# RadioMusic_B_Rev2.net
KiCad netlist of a schematic drawn in EAGLE
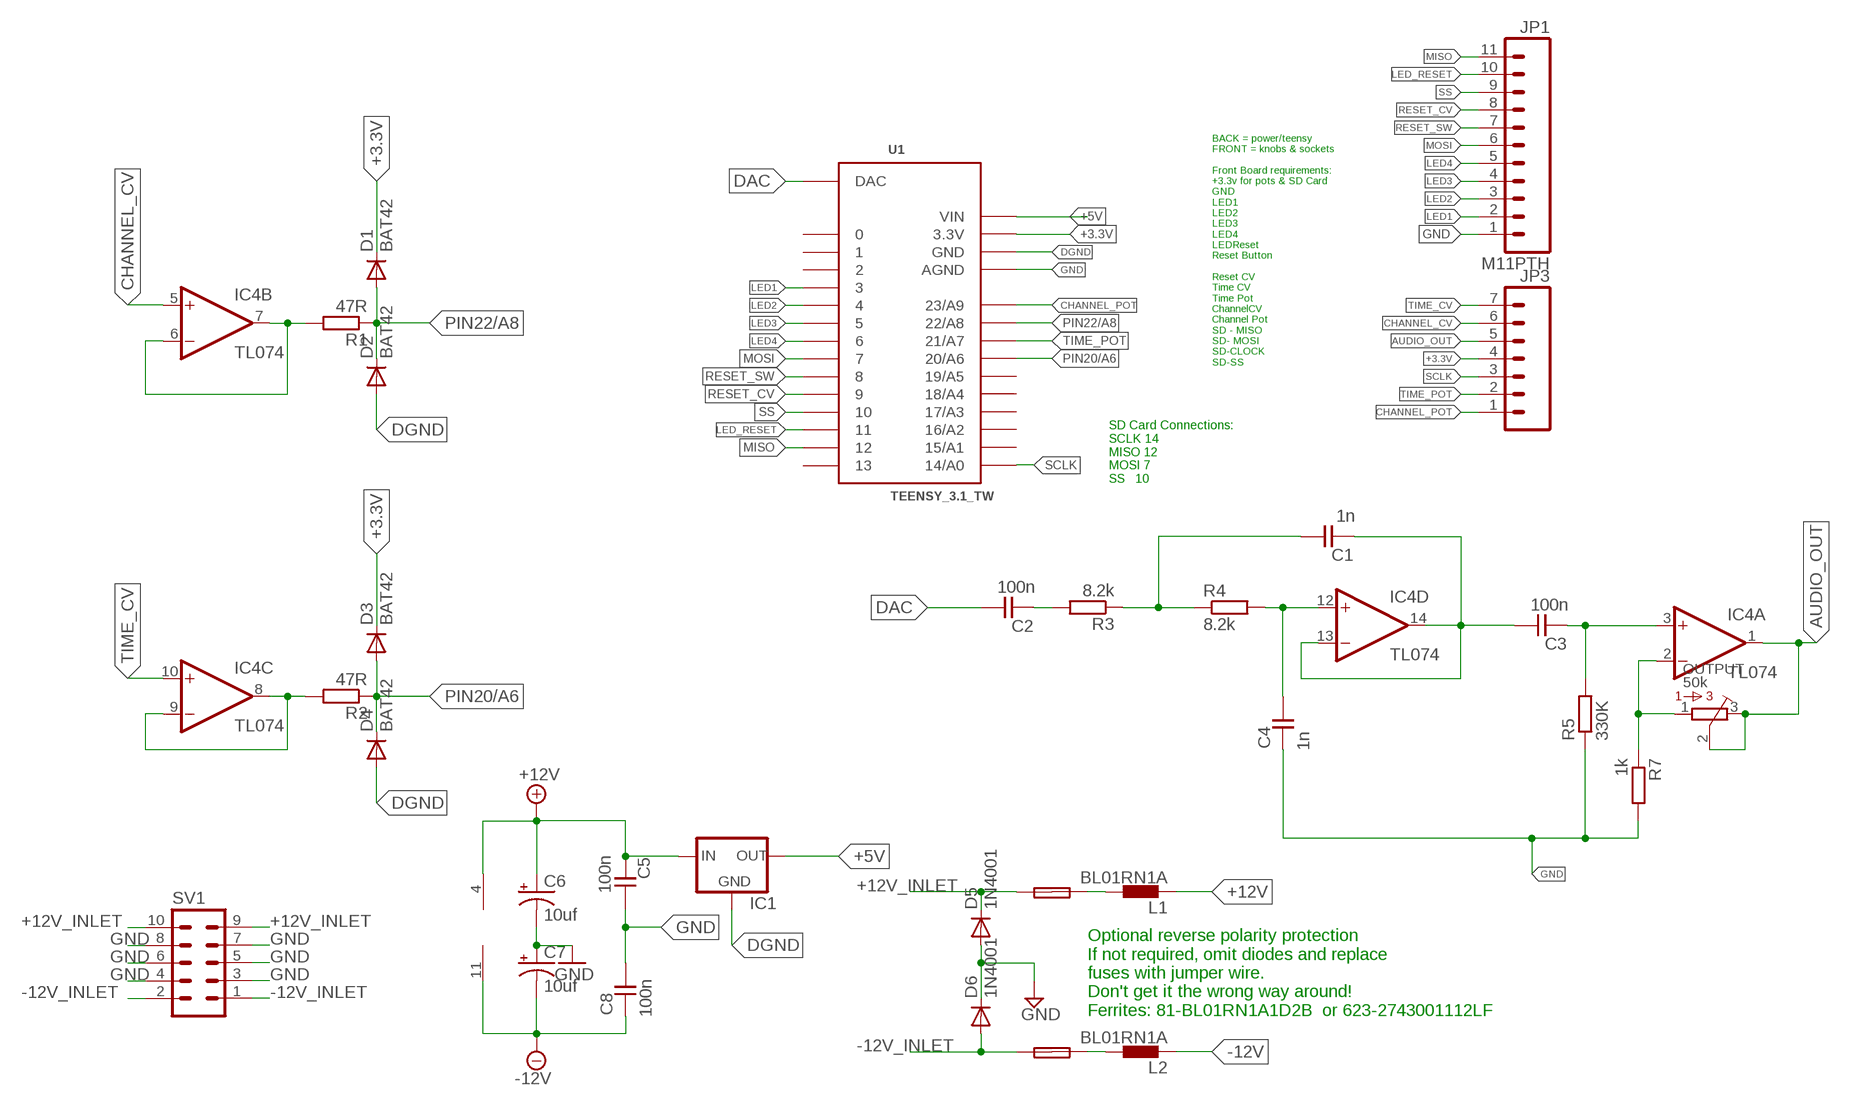
[diagram p0: schematic, sheet 1]

(export (version "E")
  (design (tool "Eeschema 10.0.6"))
  (components
    (comp (ref "C1")
      (value "1n")
      (footprint "eagle-import:C050-024X044")
      (libsource (lib "eagle-import") (part "C-EU050-024X044"))
    )
    (comp (ref "C2")
      (value "100n")
      (footprint "eagle-import:C050-025X075")
      (libsource (lib "eagle-import") (part "C-EU050-025X075"))
    )
    (comp (ref "C3")
      (value "100n")
      (footprint "eagle-import:C050-025X075")
      (libsource (lib "eagle-import") (part "C-EU050-025X075"))
    )
    (comp (ref "C4")
      (value "1n")
      (footprint "eagle-import:C050-024X044")
      (libsource (lib "eagle-import") (part "C-EU050-024X044"))
    )
    (comp (ref "C5")
      (value "100n")
      (footprint "eagle-import:C050-024X044")
      (libsource (lib "eagle-import") (part "C-EU050-024X044"))
    )
    (comp (ref "C6")
      (value "10uf")
      (footprint "eagle-import:CPOL-RADIAL-10UF-25V")
      (libsource (lib "eagle-import") (part "CAP_POLPTH2"))
    )
    (comp (ref "C7")
      (value "10uf")
      (footprint "eagle-import:CPOL-RADIAL-10UF-25V")
      (libsource (lib "eagle-import") (part "CAP_POLPTH2"))
    )
    (comp (ref "C8")
      (value "100n")
      (footprint "eagle-import:C050-024X044")
      (libsource (lib "eagle-import") (part "C-EU050-024X044"))
    )
    (comp (ref "D1")
      (value "BAT42")
      (footprint "eagle-import:DO34-7")
      (libsource (lib "eagle-import") (part "BAT81"))
    )
    (comp (ref "D2")
      (value "BAT42")
      (footprint "eagle-import:DO34-7")
      (libsource (lib "eagle-import") (part "BAT81"))
    )
    (comp (ref "D3")
      (value "BAT42")
      (footprint "eagle-import:DO34-7")
      (libsource (lib "eagle-import") (part "BAT81"))
    )
    (comp (ref "D4")
      (value "BAT42")
      (footprint "eagle-import:DO34-7")
      (libsource (lib "eagle-import") (part "BAT81"))
    )
    (comp (ref "D5")
      (value "1N4001")
      (footprint "eagle-import:DO41-10")
      (libsource (lib "eagle-import") (part "1N4004"))
    )
    (comp (ref "D6")
      (value "1N4001")
      (footprint "eagle-import:DO41-10")
      (libsource (lib "eagle-import") (part "1N4004"))
    )
    (comp (ref "F1")
      (value "FUSE")
      (footprint "eagle-import:C050H075X075")
      (libsource (lib "eagle-import") (part "PTC_FUSEPOLY_FUSE"))
    )
    (comp (ref "F2")
      (value "FUSE")
      (footprint "eagle-import:C050H075X075")
      (libsource (lib "eagle-import") (part "PTC_FUSEPOLY_FUSE"))
    )
    (comp (ref "IC1")
      (value "78LXX")
      (footprint "eagle-import:78LXX")
      (libsource (lib "eagle-import") (part "78LXX"))
    )
    (comp (ref "IC4")
      (value "TL074")
      (footprint "eagle-import:DIL14")
      (libsource (lib "eagle-import") (part "TL074P"))
    )
    (comp (ref "JP1")
      (value "M11PTH")
      (footprint "eagle-import:1X11")
      (libsource (lib "eagle-import") (part "M11PTH"))
    )
    (comp (ref "JP3")
      (value "M07")
      (footprint "eagle-import:1X07")
      (libsource (lib "eagle-import") (part "M07"))
    )
    (comp (ref "L1")
      (value "BL01RN1A")
      (footprint "eagle-import:BL01RN1A")
      (libsource (lib "eagle-import") (part "BL01RN1A"))
    )
    (comp (ref "L2")
      (value "BL01RN1A")
      (footprint "eagle-import:BL01RN1A")
      (libsource (lib "eagle-import") (part "BL01RN1A"))
    )
    (comp (ref "OUTPUT")
      (value "50k")
      (footprint "eagle-import:3362P")
      (libsource (lib "eagle-import") (part "3362P"))
    )
    (comp (ref "R1")
      (value "47R")
      (footprint "eagle-import:0207_10")
      (libsource (lib "eagle-import") (part "R-EU_STANDARD_RESISTOR"))
    )
    (comp (ref "R2")
      (value "47R")
      (footprint "eagle-import:0207_10")
      (libsource (lib "eagle-import") (part "R-EU_STANDARD_RESISTOR"))
    )
    (comp (ref "R3")
      (value "8.2k")
      (footprint "eagle-import:0207_10")
      (libsource (lib "eagle-import") (part "R-EU_STANDARD_RESISTOR"))
    )
    (comp (ref "R4")
      (value "8.2k")
      (footprint "eagle-import:0207_10")
      (libsource (lib "eagle-import") (part "R-EU_STANDARD_RESISTOR"))
    )
    (comp (ref "R5")
      (value "330K")
      (footprint "eagle-import:0207_10")
      (libsource (lib "eagle-import") (part "R-EU_STANDARD_RESISTOR"))
    )
    (comp (ref "R7")
      (value "1k")
      (footprint "eagle-import:0207_10")
      (libsource (lib "eagle-import") (part "R-EU_STANDARD_RESISTOR"))
    )
    (comp (ref "SV1")
      (value "10_PIN_HEADER")
      (footprint "eagle-import:MA05-2")
      (libsource (lib "eagle-import") (part "10_PIN_HEADER"))
    )
    (comp (ref "U1")
      (value "TEENSY_3.1_TW")
      (footprint "eagle-import:TEENSY_3.1_TW")
      (libsource (lib "eagle-import") (part "TEENSY_3.1_TW"))
    )
  )
  (nets
    (net (code "1") (name "+3.3V") (class "Default")
      (node (ref "D1") (pin "C") (pinfunction "C_C") (pintype "passive"))
      (node (ref "D3") (pin "C") (pinfunction "C_C") (pintype "passive"))
      (node (ref "JP3") (pin "4") (pinfunction "4_4") (pintype "passive"))
      (node (ref "U1") (pin "3.3V") (pinfunction "3.3V_3.3V") (pintype "power_in"))
    )
    (net (code "2") (name "+5V") (class "Default")
      (node (ref "IC1") (pin "OUT") (pinfunction "OUT_OUT") (pintype "passive"))
      (node (ref "U1") (pin "VIN") (pinfunction "VIN_VIN") (pintype "power_in"))
    )
    (net (code "3") (name "+12V") (class "Default")
      (node (ref "C5") (pin "2") (pinfunction "2_2") (pintype "passive"))
      (node (ref "C6") (pin "1") (pinfunction "+_1") (pintype "passive"))
      (node (ref "IC1") (pin "IN") (pinfunction "IN_IN") (pintype "input"))
      (node (ref "IC4") (pin "4") (pinfunction "V+_4") (pintype "power_in"))
      (node (ref "L1") (pin "1") (pinfunction "1_1") (pintype "passive"))
    )
    (net (code "4") (name "-12V") (class "Default")
      (node (ref "C7") (pin "2") (pinfunction "-_2") (pintype "passive"))
      (node (ref "C8") (pin "2") (pinfunction "2_2") (pintype "passive"))
      (node (ref "IC4") (pin "11") (pinfunction "V-_11") (pintype "power_in"))
      (node (ref "L2") (pin "1") (pinfunction "1_1") (pintype "passive"))
    )
    (net (code "5") (name "/+12V_INLET") (class "Default")
      (node (ref "D5") (pin "C") (pinfunction "C_C") (pintype "passive"))
      (node (ref "F1") (pin "1") (pinfunction "P$1_1") (pintype "bidirectional"))
      (node (ref "SV1") (pin "10") (pinfunction "10_10") (pintype "passive"))
      (node (ref "SV1") (pin "9") (pinfunction "9_9") (pintype "passive"))
    )
    (net (code "6") (name "/-12V_INLET") (class "Default")
      (node (ref "D6") (pin "A") (pinfunction "A_A") (pintype "passive"))
      (node (ref "F2") (pin "1") (pinfunction "P$1_1") (pintype "bidirectional"))
      (node (ref "SV1") (pin "1") (pinfunction "1_1") (pintype "passive"))
      (node (ref "SV1") (pin "2") (pinfunction "2_2") (pintype "passive"))
    )
    (net (code "7") (name "AUDIO_OUT") (class "Default")
      (node (ref "IC4") (pin "1") (pinfunction "OUT_1") (pintype "output"))
      (node (ref "JP3") (pin "5") (pinfunction "5_5") (pintype "passive"))
      (node (ref "OUTPUT") (pin "2") (pinfunction "2_2") (pintype "passive"))
      (node (ref "OUTPUT") (pin "3") (pinfunction "3_3") (pintype "passive"))
    )
    (net (code "8") (name "CHANNEL_CV") (class "Default")
      (node (ref "IC4") (pin "5") (pinfunction "+IN_5") (pintype "input"))
      (node (ref "JP3") (pin "6") (pinfunction "6_6") (pintype "passive"))
    )
    (net (code "9") (name "CHANNEL_POT") (class "Default")
      (node (ref "JP3") (pin "1") (pinfunction "1_1") (pintype "passive"))
      (node (ref "U1") (pin "23/A9") (pinfunction "23/A9_23/A9") (pintype "bidirectional"))
    )
    (net (code "10") (name "DAC") (class "Default")
      (node (ref "C2") (pin "1") (pinfunction "1_1") (pintype "passive"))
      (node (ref "U1") (pin "DAC") (pinfunction "DAC_DAC") (pintype "bidirectional"))
    )
    (net (code "11") (name "DGND") (class "Default")
      (node (ref "D2") (pin "A") (pinfunction "A_A") (pintype "passive"))
      (node (ref "D4") (pin "A") (pinfunction "A_A") (pintype "passive"))
      (node (ref "IC1") (pin "GND") (pinfunction "GND_GND") (pintype "input"))
      (node (ref "U1") (pin "GND") (pinfunction "GND_GND") (pintype "power_in"))
    )
    (net (code "12") (name "GND") (class "Default")
      (node (ref "C4") (pin "2") (pinfunction "2_2") (pintype "passive"))
      (node (ref "C5") (pin "1") (pinfunction "1_1") (pintype "passive"))
      (node (ref "C6") (pin "2") (pinfunction "-_2") (pintype "passive"))
      (node (ref "C7") (pin "1") (pinfunction "+_1") (pintype "passive"))
      (node (ref "C8") (pin "1") (pinfunction "1_1") (pintype "passive"))
      (node (ref "D5") (pin "A") (pinfunction "A_A") (pintype "passive"))
      (node (ref "D6") (pin "C") (pinfunction "C_C") (pintype "passive"))
      (node (ref "JP1") (pin "1") (pinfunction "1_1") (pintype "passive"))
      (node (ref "R5") (pin "1") (pinfunction "1_1") (pintype "passive"))
      (node (ref "R7") (pin "2") (pinfunction "2_2") (pintype "passive"))
      (node (ref "SV1") (pin "3") (pinfunction "3_3") (pintype "passive"))
      (node (ref "SV1") (pin "4") (pinfunction "4_4") (pintype "passive"))
      (node (ref "SV1") (pin "5") (pinfunction "5_5") (pintype "passive"))
      (node (ref "SV1") (pin "6") (pinfunction "6_6") (pintype "passive"))
      (node (ref "SV1") (pin "7") (pinfunction "7_7") (pintype "passive"))
      (node (ref "SV1") (pin "8") (pinfunction "8_8") (pintype "passive"))
      (node (ref "U1") (pin "AGND") (pinfunction "AGND_AGND") (pintype "power_in"))
    )
    (net (code "13") (name "LED1") (class "Default")
      (node (ref "JP1") (pin "2") (pinfunction "2_2") (pintype "passive"))
      (node (ref "U1") (pin "3") (pinfunction "3_3") (pintype "bidirectional"))
    )
    (net (code "14") (name "LED2") (class "Default")
      (node (ref "JP1") (pin "3") (pinfunction "3_3") (pintype "passive"))
      (node (ref "U1") (pin "4") (pinfunction "4_4") (pintype "bidirectional"))
    )
    (net (code "15") (name "LED3") (class "Default")
      (node (ref "JP1") (pin "4") (pinfunction "4_4") (pintype "passive"))
      (node (ref "U1") (pin "5") (pinfunction "5_5") (pintype "bidirectional"))
    )
    (net (code "16") (name "LED4") (class "Default")
      (node (ref "JP1") (pin "5") (pinfunction "5_5") (pintype "passive"))
      (node (ref "U1") (pin "6") (pinfunction "6_6") (pintype "bidirectional"))
    )
    (net (code "17") (name "LED_RESET") (class "Default")
      (node (ref "JP1") (pin "10") (pinfunction "10_10") (pintype "passive"))
      (node (ref "U1") (pin "11") (pinfunction "11_11") (pintype "bidirectional"))
    )
    (net (code "18") (name "MISO") (class "Default")
      (node (ref "JP1") (pin "11") (pinfunction "11_11") (pintype "passive"))
      (node (ref "U1") (pin "12") (pinfunction "12_12") (pintype "bidirectional"))
    )
    (net (code "19") (name "MOSI") (class "Default")
      (node (ref "JP1") (pin "6") (pinfunction "6_6") (pintype "passive"))
      (node (ref "U1") (pin "7") (pinfunction "7_7") (pintype "bidirectional"))
    )
    (net (code "20") (name "Net-(C1-Pad1)") (class "Default")
      (node (ref "C1") (pin "1") (pinfunction "1_1") (pintype "passive"))
      (node (ref "R3") (pin "1") (pinfunction "1_1") (pintype "passive"))
      (node (ref "R4") (pin "1") (pinfunction "1_1") (pintype "passive"))
    )
    (net (code "21") (name "Net-(C2-Pad2)") (class "Default")
      (node (ref "C2") (pin "2") (pinfunction "2_2") (pintype "passive"))
      (node (ref "R3") (pin "2") (pinfunction "2_2") (pintype "passive"))
    )
    (net (code "22") (name "Net-(F1-P$2)") (class "Default")
      (node (ref "F1") (pin "2") (pinfunction "P$2_2") (pintype "bidirectional"))
      (node (ref "L1") (pin "2") (pinfunction "2_2") (pintype "passive"))
    )
    (net (code "23") (name "Net-(F2-P$2)") (class "Default")
      (node (ref "F2") (pin "2") (pinfunction "P$2_2") (pintype "bidirectional"))
      (node (ref "L2") (pin "2") (pinfunction "2_2") (pintype "passive"))
    )
    (net (code "24") (name "Net-(IC4A-+IN)") (class "Default")
      (node (ref "C3") (pin "2") (pinfunction "2_2") (pintype "passive"))
      (node (ref "IC4") (pin "3") (pinfunction "+IN_3") (pintype "input"))
      (node (ref "R5") (pin "2") (pinfunction "2_2") (pintype "passive"))
    )
    (net (code "25") (name "Net-(IC4A--IN)") (class "Default")
      (node (ref "IC4") (pin "2") (pinfunction "-IN_2") (pintype "input"))
      (node (ref "OUTPUT") (pin "1") (pinfunction "1_1") (pintype "passive"))
      (node (ref "R7") (pin "1") (pinfunction "1_1") (pintype "passive"))
    )
    (net (code "26") (name "Net-(IC4B--IN)") (class "Default")
      (node (ref "IC4") (pin "6") (pinfunction "-IN_6") (pintype "input"))
      (node (ref "IC4") (pin "7") (pinfunction "OUT_7") (pintype "output"))
      (node (ref "R1") (pin "2") (pinfunction "2_2") (pintype "passive"))
    )
    (net (code "27") (name "Net-(IC4C--IN)") (class "Default")
      (node (ref "IC4") (pin "8") (pinfunction "OUT_8") (pintype "output"))
      (node (ref "IC4") (pin "9") (pinfunction "-IN_9") (pintype "input"))
      (node (ref "R2") (pin "2") (pinfunction "2_2") (pintype "passive"))
    )
    (net (code "28") (name "Net-(IC4D-+IN)") (class "Default")
      (node (ref "C4") (pin "1") (pinfunction "1_1") (pintype "passive"))
      (node (ref "IC4") (pin "12") (pinfunction "+IN_12") (pintype "input"))
      (node (ref "R4") (pin "2") (pinfunction "2_2") (pintype "passive"))
    )
    (net (code "29") (name "Net-(IC4D--IN)") (class "Default")
      (node (ref "C1") (pin "2") (pinfunction "2_2") (pintype "passive"))
      (node (ref "C3") (pin "1") (pinfunction "1_1") (pintype "passive"))
      (node (ref "IC4") (pin "13") (pinfunction "-IN_13") (pintype "input"))
      (node (ref "IC4") (pin "14") (pinfunction "OUT_14") (pintype "output"))
    )
    (net (code "30") (name "PIN20{slash}A6") (class "Default")
      (node (ref "D3") (pin "A") (pinfunction "A_A") (pintype "passive"))
      (node (ref "D4") (pin "C") (pinfunction "C_C") (pintype "passive"))
      (node (ref "R2") (pin "1") (pinfunction "1_1") (pintype "passive"))
      (node (ref "U1") (pin "20/A6") (pinfunction "20/A6_20/A6") (pintype "bidirectional"))
    )
    (net (code "31") (name "PIN22{slash}A8") (class "Default")
      (node (ref "D1") (pin "A") (pinfunction "A_A") (pintype "passive"))
      (node (ref "D2") (pin "C") (pinfunction "C_C") (pintype "passive"))
      (node (ref "R1") (pin "1") (pinfunction "1_1") (pintype "passive"))
      (node (ref "U1") (pin "22/A8") (pinfunction "22/A8_22/A8") (pintype "bidirectional"))
    )
    (net (code "32") (name "RESET_CV") (class "Default")
      (node (ref "JP1") (pin "8") (pinfunction "8_8") (pintype "passive"))
      (node (ref "U1") (pin "9") (pinfunction "9_9") (pintype "bidirectional"))
    )
    (net (code "33") (name "RESET_SW") (class "Default")
      (node (ref "JP1") (pin "7") (pinfunction "7_7") (pintype "passive"))
      (node (ref "U1") (pin "8") (pinfunction "8_8") (pintype "bidirectional"))
    )
    (net (code "34") (name "SCLK") (class "Default")
      (node (ref "JP3") (pin "3") (pinfunction "3_3") (pintype "passive"))
      (node (ref "U1") (pin "14/A0") (pinfunction "14/A0_14/A0") (pintype "bidirectional"))
    )
    (net (code "35") (name "SS") (class "Default")
      (node (ref "JP1") (pin "9") (pinfunction "9_9") (pintype "passive"))
      (node (ref "U1") (pin "10") (pinfunction "10_10") (pintype "bidirectional"))
    )
    (net (code "36") (name "TIME_CV") (class "Default")
      (node (ref "IC4") (pin "10") (pinfunction "+IN_10") (pintype "input"))
      (node (ref "JP3") (pin "7") (pinfunction "7_7") (pintype "passive"))
    )
    (net (code "37") (name "TIME_POT") (class "Default")
      (node (ref "JP3") (pin "2") (pinfunction "2_2") (pintype "passive"))
      (node (ref "U1") (pin "21/A7") (pinfunction "21/A7_21/A7") (pintype "bidirectional"))
    )
    (net (code "38") (name "unconnected-(U1-Pad0)") (class "Default")
      (node (ref "U1") (pin "0") (pinfunction "0_0") (pintype "bidirectional"))
    )
    (net (code "39") (name "unconnected-(U1-Pad1)") (class "Default")
      (node (ref "U1") (pin "1") (pinfunction "1_1") (pintype "bidirectional"))
    )
    (net (code "40") (name "unconnected-(U1-Pad2)") (class "Default")
      (node (ref "U1") (pin "2") (pinfunction "2_2") (pintype "bidirectional"))
    )
    (net (code "41") (name "unconnected-(U1-Pad13)") (class "Default")
      (node (ref "U1") (pin "13") (pinfunction "13_13") (pintype "bidirectional"))
    )
    (net (code "42") (name "unconnected-(U1-Pad15{slash}A1)") (class "Default")
      (node (ref "U1") (pin "15/A1") (pinfunction "15/A1_15/A1") (pintype "bidirectional"))
    )
    (net (code "43") (name "unconnected-(U1-Pad16{slash}A2)") (class "Default")
      (node (ref "U1") (pin "16/A2") (pinfunction "16/A2_16/A2") (pintype "bidirectional"))
    )
    (net (code "44") (name "unconnected-(U1-Pad17{slash}A3)") (class "Default")
      (node (ref "U1") (pin "17/A3") (pinfunction "17/A3_17/A3") (pintype "bidirectional"))
    )
    (net (code "45") (name "unconnected-(U1-Pad18{slash}A4)") (class "Default")
      (node (ref "U1") (pin "18/A4") (pinfunction "18/A4_18/A4") (pintype "bidirectional"))
    )
    (net (code "46") (name "unconnected-(U1-Pad19{slash}A5)") (class "Default")
      (node (ref "U1") (pin "19/A5") (pinfunction "19/A5_19/A5") (pintype "bidirectional"))
    )
  )
)
